# ioh-landscape.net
KiCad netlist of a schematic drawn in EAGLE
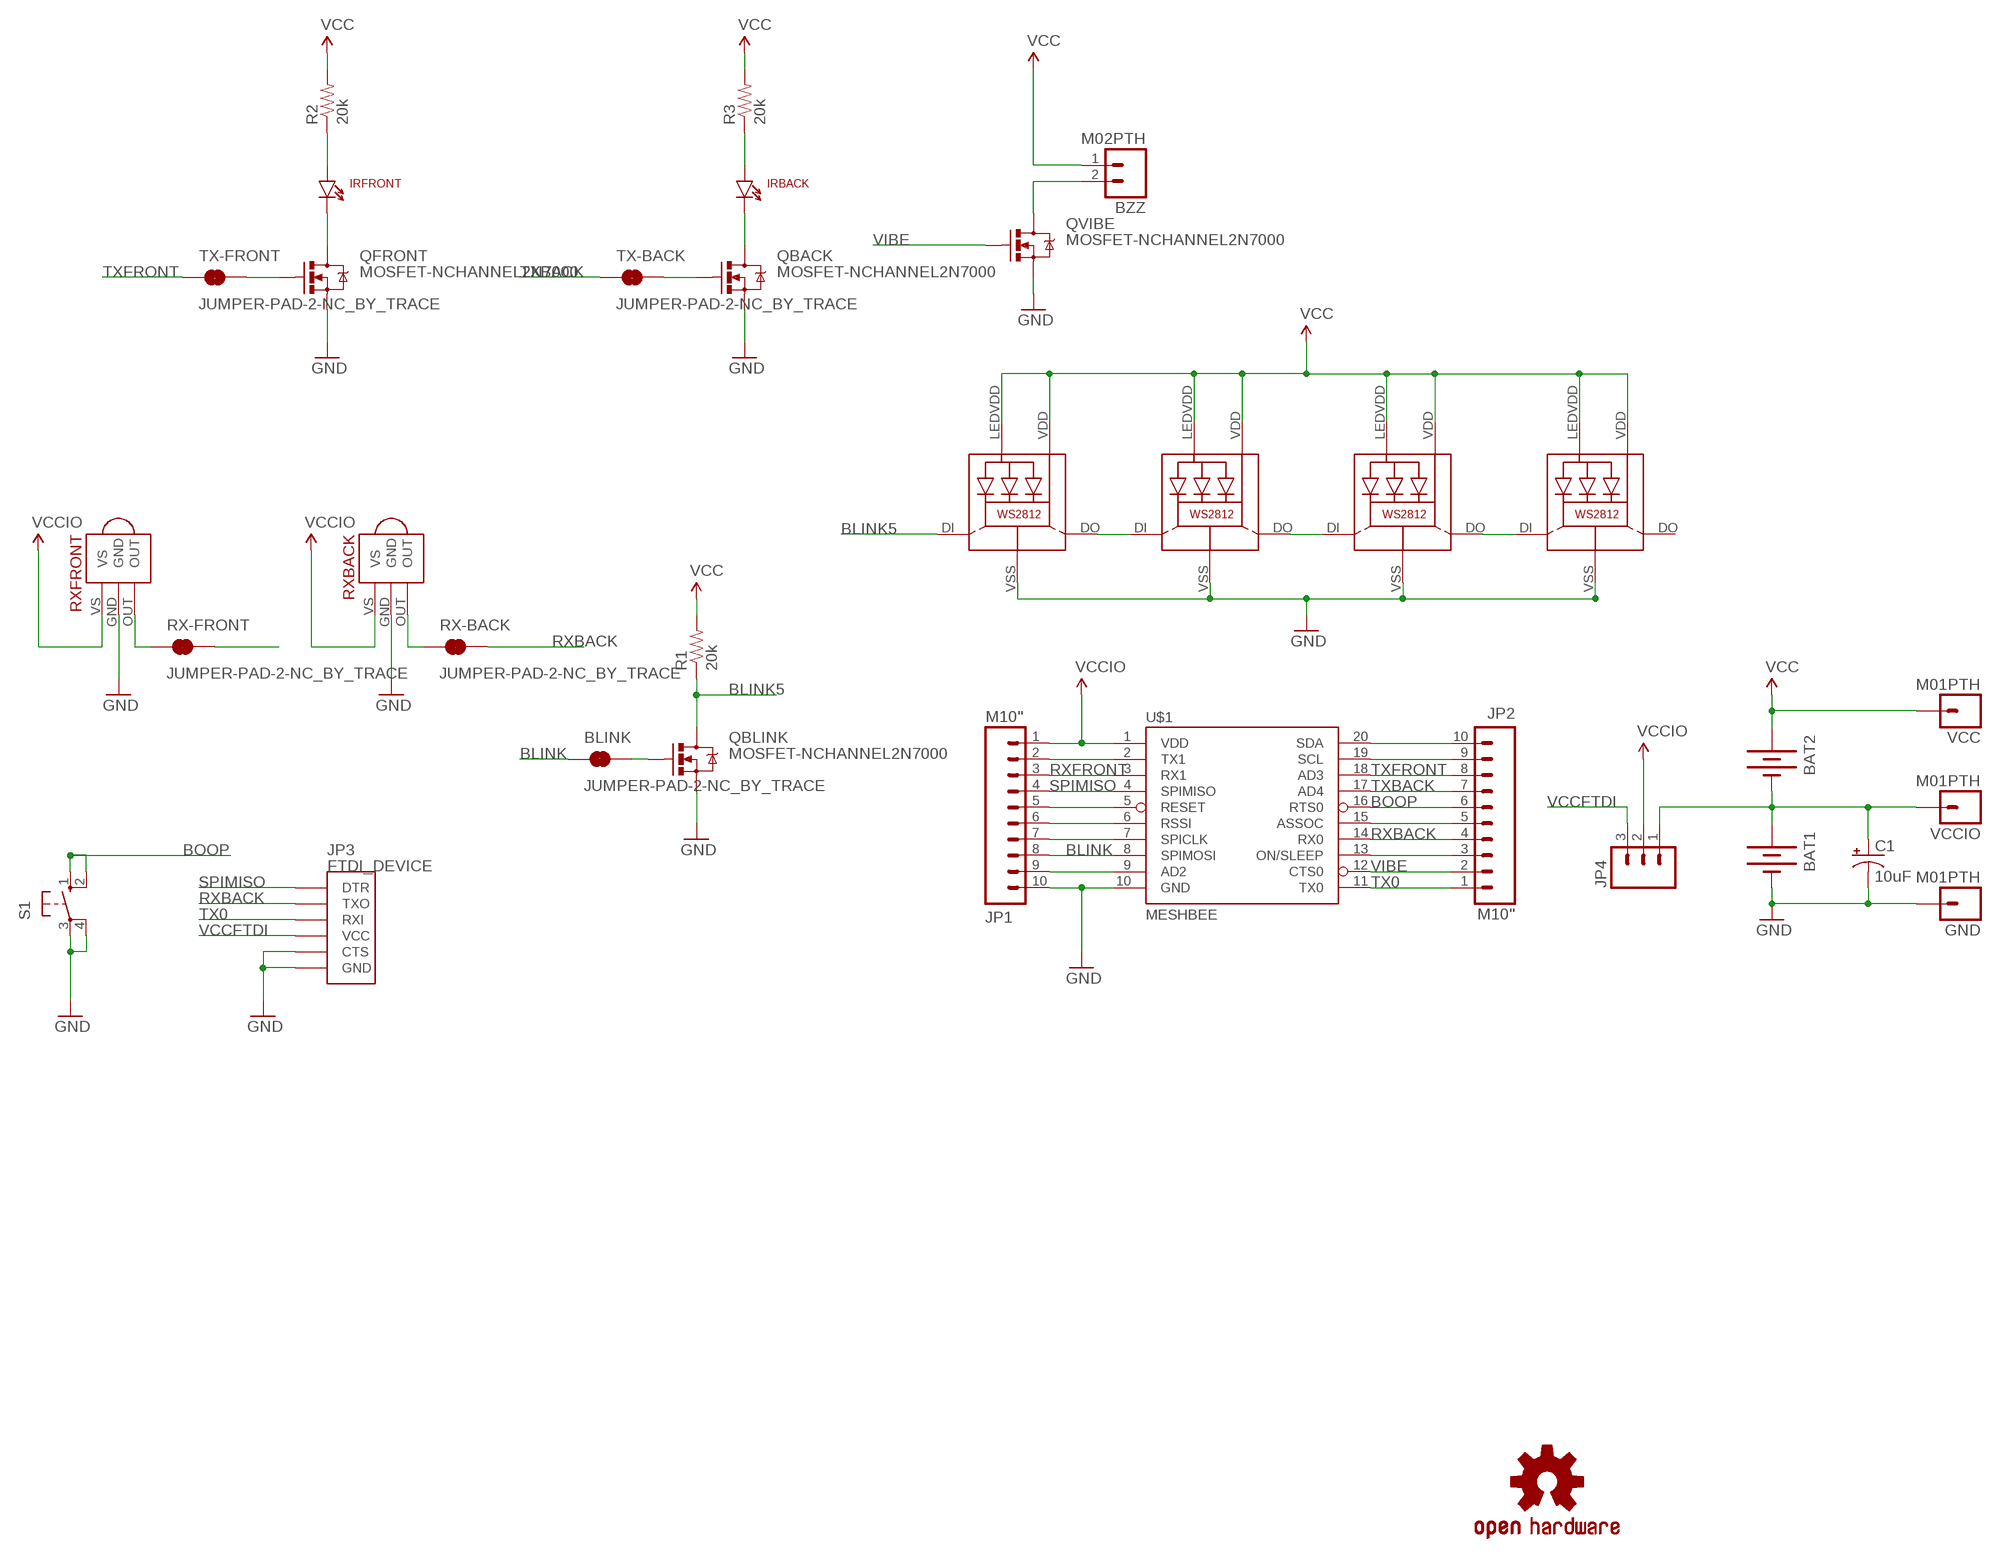
[diagram p0: schematic, sheet 1]

(export (version "E")
  (design (tool "Eeschema 10.0.6"))
  (components
    (comp (ref "BAT1")
      (value "BATTERY20PTH")
      (footprint "eagle-import:BATTCOM_20MM_PTH")
      (libsource (lib "eagle-import") (part "BATTERY20PTH"))
    )
    (comp (ref "BAT2")
      (value "BATTERY20PTH")
      (footprint "eagle-import:BATTCOM_20MM_PTH")
      (libsource (lib "eagle-import") (part "BATTERY20PTH"))
    )
    (comp (ref "BLINK")
      (value "JUMPER-PAD-2-NC_BY_TRACE")
      (footprint "eagle-import:PAD-JUMPER-2-NC_BY_TRACE_YES_SILK")
      (libsource (lib "eagle-import") (part "JUMPER-PAD-2-NC_BY_TRACE"))
    )
    (comp (ref "BZZ")
      (value "M02PTH")
      (footprint "eagle-import:1X02")
      (libsource (lib "eagle-import") (part "M02PTH"))
    )
    (comp (ref "C1")
      (value "10uF")
      (footprint "eagle-import:CPOL-RADIAL-10UF-25V-KIT")
      (libsource (lib "eagle-import") (part "10UF-25V-20%(PTH)KIT"))
    )
    (comp (ref "GND")
      (value "M01PTH")
      (footprint "eagle-import:1X01")
      (libsource (lib "eagle-import") (part "M01PTH"))
    )
    (comp (ref "IRBACK")
      (value "LTE-302")
      (footprint "eagle-import:LTE-302")
      (libsource (lib "eagle-import") (part "LTE-302"))
    )
    (comp (ref "IRFRONT")
      (value "LTE-302")
      (footprint "eagle-import:LTE-302")
      (libsource (lib "eagle-import") (part "LTE-302"))
    )
    (comp (ref "JP1")
      (value "M10\"")
      (footprint "eagle-import:1X10")
      (libsource (lib "eagle-import") (part "M10{dblquote}"))
    )
    (comp (ref "JP2")
      (value "M10\"")
      (footprint "eagle-import:1X10")
      (libsource (lib "eagle-import") (part "M10{dblquote}"))
    )
    (comp (ref "JP3")
      (value "FTDI_DEVICE")
      (footprint "eagle-import:FTDI_DEVICE_SIDE")
      (libsource (lib "eagle-import") (part "FTDI_DEVICE"))
    )
    (comp (ref "JP4")
      (value "M03LOCK")
      (footprint "eagle-import:1X03_LOCK")
      (libsource (lib "eagle-import") (part "M03LOCK"))
    )
    (comp (ref "LED2")
      (value "WS2812")
      (footprint "eagle-import:WS2812")
      (libsource (lib "eagle-import") (part "WS2812"))
    )
    (comp (ref "LED3")
      (value "WS2812")
      (footprint "eagle-import:WS2812")
      (libsource (lib "eagle-import") (part "WS2812"))
    )
    (comp (ref "LED4")
      (value "WS2812")
      (footprint "eagle-import:WS2812")
      (libsource (lib "eagle-import") (part "WS2812"))
    )
    (comp (ref "LED5")
      (value "WS2812")
      (footprint "eagle-import:WS2812")
      (libsource (lib "eagle-import") (part "WS2812"))
    )
    (comp (ref "LOGO1")
      (value "OSHW-LOGOS")
      (footprint "eagle-import:OSHW-LOGO-S")
      (libsource (lib "eagle-import") (part "OSHW-LOGOS"))
    )
    (comp (ref "QBACK")
      (value "MOSFET-NCHANNEL2N7000")
      (footprint "eagle-import:TO-92")
      (libsource (lib "eagle-import") (part "MOSFET-NCHANNEL2N7000"))
    )
    (comp (ref "QBLINK")
      (value "MOSFET-NCHANNEL2N7000")
      (footprint "eagle-import:TO-92")
      (libsource (lib "eagle-import") (part "MOSFET-NCHANNEL2N7000"))
    )
    (comp (ref "QFRONT")
      (value "MOSFET-NCHANNEL2N7000")
      (footprint "eagle-import:TO-92")
      (libsource (lib "eagle-import") (part "MOSFET-NCHANNEL2N7000"))
    )
    (comp (ref "QVIBE")
      (value "MOSFET-NCHANNEL2N7000")
      (footprint "eagle-import:TO-92")
      (libsource (lib "eagle-import") (part "MOSFET-NCHANNEL2N7000"))
    )
    (comp (ref "R1")
      (value "20k")
      (footprint "eagle-import:AXIAL-0.4")
      (libsource (lib "eagle-import") (part "RESISTORPTH-1/4W"))
    )
    (comp (ref "R2")
      (value "20k")
      (footprint "eagle-import:AXIAL-0.4")
      (libsource (lib "eagle-import") (part "RESISTORPTH-1/4W"))
    )
    (comp (ref "R3")
      (value "20k")
      (footprint "eagle-import:AXIAL-0.4")
      (libsource (lib "eagle-import") (part "RESISTORPTH-1/4W"))
    )
    (comp (ref "RX-BACK")
      (value "JUMPER-PAD-2-NC_BY_TRACE")
      (footprint "eagle-import:PAD-JUMPER-2-NC_BY_TRACE_YES_SILK")
      (libsource (lib "eagle-import") (part "JUMPER-PAD-2-NC_BY_TRACE"))
    )
    (comp (ref "RX-FRONT")
      (value "JUMPER-PAD-2-NC_BY_TRACE")
      (footprint "eagle-import:PAD-JUMPER-2-NC_BY_TRACE_YES_SILK")
      (libsource (lib "eagle-import") (part "JUMPER-PAD-2-NC_BY_TRACE"))
    )
    (comp (ref "RXBACK")
      (value "TSOP2438")
      (footprint "eagle-import:TSOP2438")
      (libsource (lib "eagle-import") (part "TSOP2438"))
    )
    (comp (ref "RXFRONT")
      (value "TSOP2438")
      (footprint "eagle-import:TSOP2438")
      (libsource (lib "eagle-import") (part "TSOP2438"))
    )
    (comp (ref "S1")
      (value "40-XX")
      (footprint "eagle-import:B3F-40XX")
      (fields (field (name "MF") "OMRON COMPONENTS USA") (field (name "MPN") "B3F-4000"))
      (libsource (lib "eagle-import") (part "40-XX"))
    )
    (comp (ref "TX-BACK")
      (value "JUMPER-PAD-2-NC_BY_TRACE")
      (footprint "eagle-import:PAD-JUMPER-2-NC_BY_TRACE_YES_SILK")
      (libsource (lib "eagle-import") (part "JUMPER-PAD-2-NC_BY_TRACE"))
    )
    (comp (ref "TX-FRONT")
      (value "JUMPER-PAD-2-NC_BY_TRACE")
      (footprint "eagle-import:PAD-JUMPER-2-NC_BY_TRACE_YES_SILK")
      (libsource (lib "eagle-import") (part "JUMPER-PAD-2-NC_BY_TRACE"))
    )
    (comp (ref "U$1")
      (value "MESHBEE")
      (footprint "eagle-import:MESHBEE")
      (libsource (lib "eagle-import") (part "MESHBEE"))
    )
    (comp (ref "VCC")
      (value "M01PTH")
      (footprint "eagle-import:1X01")
      (libsource (lib "eagle-import") (part "M01PTH"))
    )
    (comp (ref "VCCIO")
      (value "M01PTH")
      (footprint "eagle-import:1X01")
      (libsource (lib "eagle-import") (part "M01PTH"))
    )
  )
  (nets
    (net (code "1") (name "/BLINK") (class "Default")
      (node (ref "BLINK") (pin "1") (pinfunction "1_1") (pintype "passive"))
      (node (ref "JP1") (pin "8") (pinfunction "8_8") (pintype "passive"))
      (node (ref "U$1") (pin "8") (pinfunction "SPIMOSI_8") (pintype "bidirectional"))
    )
    (net (code "2") (name "/BLINK5") (class "Default")
      (node (ref "LED2") (pin "DI") (pinfunction "DI_DI") (pintype "input"))
      (node (ref "QBLINK") (pin "3") (pinfunction "D_3") (pintype "passive"))
      (node (ref "R1") (pin "P$1") (pinfunction "1_P$1") (pintype "passive"))
    )
    (net (code "3") (name "/BOOP") (class "Default")
      (node (ref "JP2") (pin "6") (pinfunction "6_6") (pintype "passive"))
      (node (ref "S1") (pin "1") (pinfunction "S_1") (pintype "passive"))
      (node (ref "S1") (pin "2") (pinfunction "S1_2") (pintype "passive"))
      (node (ref "U$1") (pin "16") (pinfunction "RTS0_16") (pintype "input"))
    )
    (net (code "4") (name "/RXBACK") (class "Default")
      (node (ref "JP2") (pin "4") (pinfunction "4_4") (pintype "passive"))
      (node (ref "JP3") (pin "P$2") (pinfunction "TXO_P$2") (pintype "bidirectional"))
      (node (ref "RX-BACK") (pin "2") (pinfunction "2_2") (pintype "passive"))
      (node (ref "U$1") (pin "14") (pinfunction "RX0_14") (pintype "bidirectional"))
    )
    (net (code "5") (name "/RXFRONT") (class "Default")
      (node (ref "JP1") (pin "3") (pinfunction "3_3") (pintype "passive"))
      (node (ref "RX-FRONT") (pin "2") (pinfunction "2_2") (pintype "passive"))
      (node (ref "U$1") (pin "3") (pinfunction "RX1_3") (pintype "input"))
    )
    (net (code "6") (name "/SPIMISO") (class "Default")
      (node (ref "JP1") (pin "4") (pinfunction "4_4") (pintype "passive"))
      (node (ref "JP3") (pin "P$1") (pinfunction "DTR_P$1") (pintype "bidirectional"))
      (node (ref "U$1") (pin "4") (pinfunction "SPIMISO_4") (pintype "bidirectional"))
    )
    (net (code "7") (name "/TX0") (class "Default")
      (node (ref "JP2") (pin "1") (pinfunction "1_1") (pintype "passive"))
      (node (ref "JP3") (pin "P$3") (pinfunction "RXI_P$3") (pintype "bidirectional"))
      (node (ref "U$1") (pin "11") (pinfunction "TX0_11") (pintype "bidirectional"))
    )
    (net (code "8") (name "/TXBACK") (class "Default")
      (node (ref "JP2") (pin "7") (pinfunction "7_7") (pintype "passive"))
      (node (ref "TX-BACK") (pin "1") (pinfunction "1_1") (pintype "passive"))
      (node (ref "U$1") (pin "17") (pinfunction "AD4_17") (pintype "bidirectional"))
    )
    (net (code "9") (name "/TXFRONT") (class "Default")
      (node (ref "JP2") (pin "8") (pinfunction "8_8") (pintype "passive"))
      (node (ref "TX-FRONT") (pin "1") (pinfunction "1_1") (pintype "passive"))
      (node (ref "U$1") (pin "18") (pinfunction "AD3_18") (pintype "bidirectional"))
    )
    (net (code "10") (name "/VCCFTDI") (class "Default")
      (node (ref "JP3") (pin "P$4") (pinfunction "VCC_P$4") (pintype "bidirectional"))
      (node (ref "JP4") (pin "3") (pinfunction "3_3") (pintype "passive"))
    )
    (net (code "11") (name "/VIBE") (class "Default")
      (node (ref "JP2") (pin "2") (pinfunction "2_2") (pintype "passive"))
      (node (ref "QVIBE") (pin "2") (pinfunction "G_2") (pintype "passive"))
      (node (ref "U$1") (pin "12") (pinfunction "CTS0_12") (pintype "output"))
    )
    (net (code "12") (name "GND") (class "Default")
      (node (ref "BAT1") (pin "2") (pinfunction "-_2") (pintype "power_in"))
      (node (ref "C1") (pin "2") (pinfunction "-_2") (pintype "passive"))
      (node (ref "GND") (pin "1") (pinfunction "1_1") (pintype "passive"))
      (node (ref "JP1") (pin "10") (pinfunction "10_10") (pintype "passive"))
      (node (ref "JP3") (pin "P$5") (pinfunction "CTS_P$5") (pintype "bidirectional"))
      (node (ref "JP3") (pin "P$6") (pinfunction "GND_P$6") (pintype "bidirectional"))
      (node (ref "LED2") (pin "VSS") (pinfunction "GND_VSS") (pintype "power_in"))
      (node (ref "LED3") (pin "VSS") (pinfunction "GND_VSS") (pintype "power_in"))
      (node (ref "LED4") (pin "VSS") (pinfunction "GND_VSS") (pintype "power_in"))
      (node (ref "LED5") (pin "VSS") (pinfunction "GND_VSS") (pintype "power_in"))
      (node (ref "QBACK") (pin "1") (pinfunction "S_1") (pintype "passive"))
      (node (ref "QBLINK") (pin "1") (pinfunction "S_1") (pintype "passive"))
      (node (ref "QFRONT") (pin "1") (pinfunction "S_1") (pintype "passive"))
      (node (ref "QVIBE") (pin "1") (pinfunction "S_1") (pintype "passive"))
      (node (ref "RXBACK") (pin "GND") (pinfunction "GND_GND") (pintype "power_in"))
      (node (ref "RXFRONT") (pin "GND") (pinfunction "GND_GND") (pintype "power_in"))
      (node (ref "S1") (pin "3") (pinfunction "P_3") (pintype "passive"))
      (node (ref "S1") (pin "4") (pinfunction "P1_4") (pintype "passive"))
      (node (ref "U$1") (pin "10") (pinfunction "GND_10") (pintype "power_in"))
    )
    (net (code "13") (name "Net-(BAT1-+)") (class "Default")
      (node (ref "BAT1") (pin "1") (pinfunction "+_1") (pintype "power_in"))
      (node (ref "BAT2") (pin "2") (pinfunction "-_2") (pintype "power_in"))
      (node (ref "C1") (pin "1") (pinfunction "+_1") (pintype "passive"))
      (node (ref "JP4") (pin "1") (pinfunction "1_1") (pintype "passive"))
      (node (ref "VCCIO") (pin "1") (pinfunction "1_1") (pintype "passive"))
    )
    (net (code "14") (name "Net-(LED2-PadDO)") (class "Default")
      (node (ref "LED2") (pin "DO") (pinfunction "DO_DO") (pintype "output"))
      (node (ref "LED3") (pin "DI") (pinfunction "DI_DI") (pintype "input"))
    )
    (net (code "15") (name "Net-(LED3-PadDO)") (class "Default")
      (node (ref "LED3") (pin "DO") (pinfunction "DO_DO") (pintype "output"))
      (node (ref "LED4") (pin "DI") (pinfunction "DI_DI") (pintype "input"))
    )
    (net (code "16") (name "Net-(LED4-PadDO)") (class "Default")
      (node (ref "LED4") (pin "DO") (pinfunction "DO_DO") (pintype "output"))
      (node (ref "LED5") (pin "DI") (pinfunction "DI_DI") (pintype "input"))
    )
    (net (code "17") (name "Net-(QBACK-D)") (class "Default")
      (node (ref "IRBACK") (pin "C") (pinfunction "C_C") (pintype "bidirectional"))
      (node (ref "QBACK") (pin "3") (pinfunction "D_3") (pintype "passive"))
    )
    (net (code "18") (name "Net-(QBACK-G)") (class "Default")
      (node (ref "QBACK") (pin "2") (pinfunction "G_2") (pintype "passive"))
      (node (ref "TX-BACK") (pin "2") (pinfunction "2_2") (pintype "passive"))
    )
    (net (code "19") (name "Net-(QBLINK-G)") (class "Default")
      (node (ref "BLINK") (pin "2") (pinfunction "2_2") (pintype "passive"))
      (node (ref "QBLINK") (pin "2") (pinfunction "G_2") (pintype "passive"))
    )
    (net (code "20") (name "Net-(QFRONT-D)") (class "Default")
      (node (ref "IRFRONT") (pin "C") (pinfunction "C_C") (pintype "bidirectional"))
      (node (ref "QFRONT") (pin "3") (pinfunction "D_3") (pintype "passive"))
    )
    (net (code "21") (name "Net-(QFRONT-G)") (class "Default")
      (node (ref "QFRONT") (pin "2") (pinfunction "G_2") (pintype "passive"))
      (node (ref "TX-FRONT") (pin "2") (pinfunction "2_2") (pintype "passive"))
    )
    (net (code "22") (name "Net-(QVIBE-D)") (class "Default")
      (node (ref "BZZ") (pin "2") (pinfunction "2_2") (pintype "passive"))
      (node (ref "QVIBE") (pin "3") (pinfunction "D_3") (pintype "passive"))
    )
    (net (code "23") (name "Net-(R2-1)") (class "Default")
      (node (ref "IRFRONT") (pin "A") (pinfunction "A_A") (pintype "bidirectional"))
      (node (ref "R2") (pin "P$1") (pinfunction "1_P$1") (pintype "passive"))
    )
    (net (code "24") (name "Net-(R3-1)") (class "Default")
      (node (ref "IRBACK") (pin "A") (pinfunction "A_A") (pintype "bidirectional"))
      (node (ref "R3") (pin "P$1") (pinfunction "1_P$1") (pintype "passive"))
    )
    (net (code "25") (name "Net-(RX-BACK-Pad1)") (class "Default")
      (node (ref "RX-BACK") (pin "1") (pinfunction "1_1") (pintype "passive"))
      (node (ref "RXBACK") (pin "OUT") (pinfunction "OUT_OUT") (pintype "output"))
    )
    (net (code "26") (name "Net-(RX-FRONT-Pad1)") (class "Default")
      (node (ref "RX-FRONT") (pin "1") (pinfunction "1_1") (pintype "passive"))
      (node (ref "RXFRONT") (pin "OUT") (pinfunction "OUT_OUT") (pintype "output"))
    )
    (net (code "27") (name "Net-(U$1-AD2)") (class "Default")
      (node (ref "JP1") (pin "9") (pinfunction "9_9") (pintype "passive"))
      (node (ref "U$1") (pin "9") (pinfunction "AD2_9") (pintype "bidirectional"))
    )
    (net (code "28") (name "Net-(U$1-ASSOC)") (class "Default")
      (node (ref "JP2") (pin "5") (pinfunction "5_5") (pintype "passive"))
      (node (ref "U$1") (pin "15") (pinfunction "ASSOC_15") (pintype "bidirectional"))
    )
    (net (code "29") (name "Net-(U$1-ON{slash}SLEEP)") (class "Default")
      (node (ref "JP2") (pin "3") (pinfunction "3_3") (pintype "passive"))
      (node (ref "U$1") (pin "13") (pinfunction "ON/SLEEP_13") (pintype "bidirectional"))
    )
    (net (code "30") (name "Net-(U$1-RESET)") (class "Default")
      (node (ref "JP1") (pin "5") (pinfunction "5_5") (pintype "passive"))
      (node (ref "U$1") (pin "5") (pinfunction "RESET_5") (pintype "input"))
    )
    (net (code "31") (name "Net-(U$1-RSSI)") (class "Default")
      (node (ref "JP1") (pin "6") (pinfunction "6_6") (pintype "passive"))
      (node (ref "U$1") (pin "6") (pinfunction "RSSI_6") (pintype "bidirectional"))
    )
    (net (code "32") (name "Net-(U$1-SCL)") (class "Default")
      (node (ref "JP2") (pin "9") (pinfunction "9_9") (pintype "passive"))
      (node (ref "U$1") (pin "19") (pinfunction "SCL_19") (pintype "bidirectional"))
    )
    (net (code "33") (name "Net-(U$1-SDA)") (class "Default")
      (node (ref "JP2") (pin "10") (pinfunction "10_10") (pintype "passive"))
      (node (ref "U$1") (pin "20") (pinfunction "SDA_20") (pintype "bidirectional"))
    )
    (net (code "34") (name "Net-(U$1-SPICLK)") (class "Default")
      (node (ref "JP1") (pin "7") (pinfunction "7_7") (pintype "passive"))
      (node (ref "U$1") (pin "7") (pinfunction "SPICLK_7") (pintype "bidirectional"))
    )
    (net (code "35") (name "Net-(U$1-TX1)") (class "Default")
      (node (ref "JP1") (pin "2") (pinfunction "2_2") (pintype "passive"))
      (node (ref "U$1") (pin "2") (pinfunction "TX1_2") (pintype "output"))
    )
    (net (code "36") (name "VCC") (class "Default")
      (node (ref "BAT2") (pin "1") (pinfunction "+_1") (pintype "power_in"))
      (node (ref "BZZ") (pin "1") (pinfunction "1_1") (pintype "passive"))
      (node (ref "LED2") (pin "LEDVDD") (pinfunction "LEDVDD_LEDVDD") (pintype "power_in"))
      (node (ref "LED2") (pin "VDD") (pinfunction "VDD_VDD") (pintype "power_in"))
      (node (ref "LED3") (pin "LEDVDD") (pinfunction "LEDVDD_LEDVDD") (pintype "power_in"))
      (node (ref "LED3") (pin "VDD") (pinfunction "VDD_VDD") (pintype "power_in"))
      (node (ref "LED4") (pin "LEDVDD") (pinfunction "LEDVDD_LEDVDD") (pintype "power_in"))
      (node (ref "LED4") (pin "VDD") (pinfunction "VDD_VDD") (pintype "power_in"))
      (node (ref "LED5") (pin "LEDVDD") (pinfunction "LEDVDD_LEDVDD") (pintype "power_in"))
      (node (ref "LED5") (pin "VDD") (pinfunction "VDD_VDD") (pintype "power_in"))
      (node (ref "R1") (pin "P$2") (pinfunction "2_P$2") (pintype "passive"))
      (node (ref "R2") (pin "P$2") (pinfunction "2_P$2") (pintype "passive"))
      (node (ref "R3") (pin "P$2") (pinfunction "2_P$2") (pintype "passive"))
      (node (ref "VCC") (pin "1") (pinfunction "1_1") (pintype "passive"))
    )
    (net (code "37") (name "VCCIO") (class "Default")
      (node (ref "JP1") (pin "1") (pinfunction "1_1") (pintype "passive"))
      (node (ref "JP4") (pin "2") (pinfunction "2_2") (pintype "passive"))
      (node (ref "RXBACK") (pin "VS") (pinfunction "VS_VS") (pintype "power_in"))
      (node (ref "RXFRONT") (pin "VS") (pinfunction "VS_VS") (pintype "power_in"))
      (node (ref "U$1") (pin "1") (pinfunction "VDD_1") (pintype "power_in"))
    )
    (net (code "38") (name "unconnected-(LED5-PadDO)") (class "Default")
      (node (ref "LED5") (pin "DO") (pinfunction "DO_DO") (pintype "output"))
    )
  )
)
